# btn_single_V1_0.net
KiCad netlist of a schematic drawn in Altium Designer
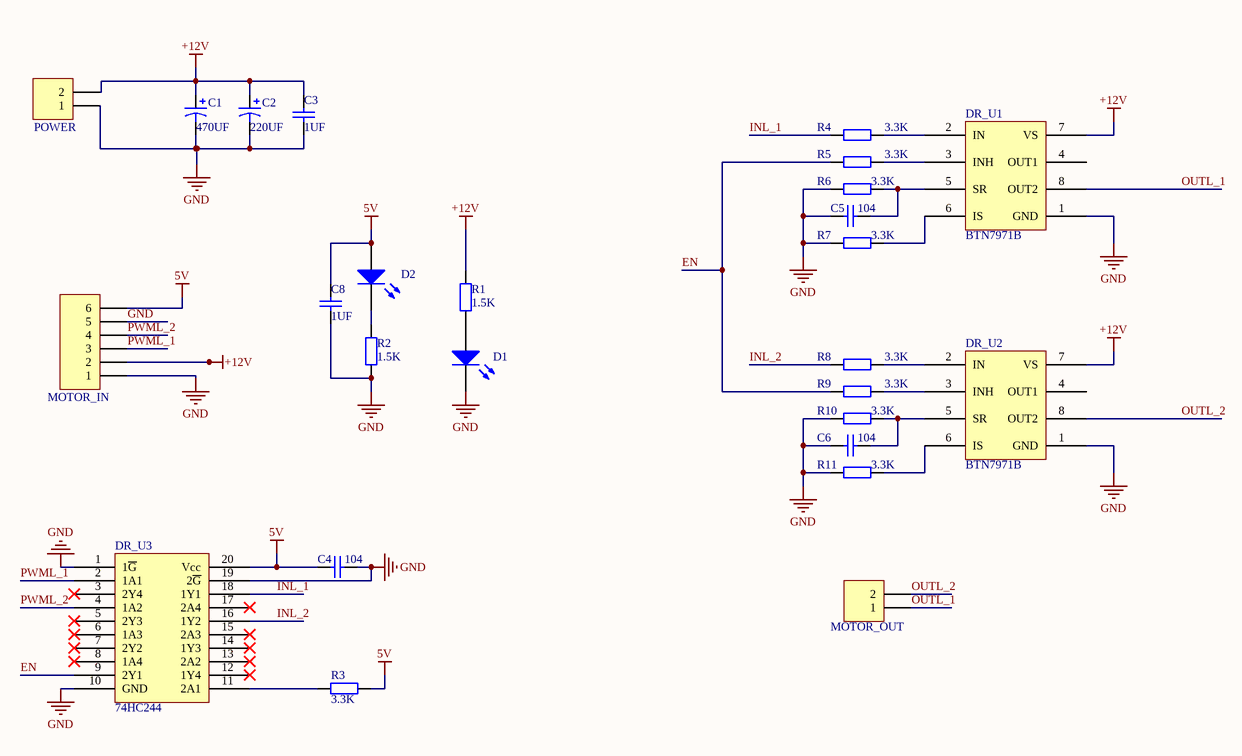
[diagram p0: btn_single_V1.0.SchDoc]

(export (version "E")
  (design (tool "Eeschema 10.0.6"))
  (components
    (comp (ref "C1")
      (value "470UF")
      (footprint "CAP 5.0*10*12.5")
      (description "Polarized Capacitor (Radial)")
      (fields (field (name "Comment") "Cap Pol1") (field (name "PUBLISHER") "Altium Limited"))
      (libsource (lib "Miscellaneous Devices") (part "Cap Pol1"))
    )
    (comp (ref "C2")
      (value "220UF")
      (footprint "CAP 2.5*6.3*7")
      (description "Polarized Capacitor (Radial)")
      (fields (field (name "Comment") "Cap Pol1") (field (name "PUBLISHER") "Altium Limited"))
      (libsource (lib "Miscellaneous Devices") (part "Cap Pol1"))
    )
    (comp (ref "C3")
      (value "1UF")
      (footprint "C 0603_L")
      (description "Capacitor")
      (fields (field (name "Comment") "Cap") (field (name "PUBLISHER") "Altium Limited"))
      (libsource (lib "Miscellaneous Devices") (part "Cap"))
    )
    (comp (ref "C4")
      (value "104")
      (footprint "C 0603_L")
      (description "Capacitor")
      (fields (field (name "Comment") "Cap") (field (name "PUBLISHER") "Altium Limited"))
      (libsource (lib "Miscellaneous Devices") (part "Cap"))
    )
    (comp (ref "C5")
      (value "104")
      (footprint "C 0603_L")
      (description "Capacitor")
      (fields (field (name "Comment") "Cap") (field (name "PUBLISHER") "Altium Limited"))
      (libsource (lib "Miscellaneous Devices") (part "Cap"))
    )
    (comp (ref "C6")
      (value "104")
      (footprint "C 0603_L")
      (description "Capacitor")
      (fields (field (name "Comment") "Cap") (field (name "PUBLISHER") "Altium Limited"))
      (libsource (lib "Miscellaneous Devices") (part "Cap"))
    )
    (comp (ref "C8")
      (value "1UF")
      (footprint "C 0603_L")
      (description "Capacitor")
      (fields (field (name "Comment") "Cap") (field (name "PUBLISHER") "Altium Limited"))
      (libsource (lib "Miscellaneous Devices") (part "Cap"))
    )
    (comp (ref "D1")
      (value "LED2")
      (footprint "0603LED B")
      (description "Typical RED, GREEN, YELLOW, AMBER GaAs LED")
      (fields (field (name "PUBLISHER") "Altium Limited"))
      (libsource (lib "Miscellaneous Devices") (part "LED2"))
    )
    (comp (ref "D2")
      (value "LED2")
      (footprint "0603LED B")
      (description "Typical RED, GREEN, YELLOW, AMBER GaAs LED")
      (fields (field (name "PUBLISHER") "Altium Limited"))
      (libsource (lib "Miscellaneous Devices") (part "LED2"))
    )
    (comp (ref "DR_U1") (value "BTN7971B") (footprint "BTN") (libsource (lib "Driver") (part "BTN7971B")))
    (comp (ref "DR_U2") (value "BTN7971B") (footprint "BTN") (libsource (lib "Driver") (part "BTN7971B")))
    (comp (ref "DR_U3") (value "74HC244") (footprint "SOP20_N") (libsource (lib "Driver") (part "74HC244")))
    (comp (ref "MOTOR_IN")
      (value "Header 6")
      (footprint "MX 1.25-WI-6P")
      (description "Header, 6-Pin")
      (fields (field (name "PUBLISHER") "Altium Limited"))
      (libsource (lib "Miscellaneous Connectors") (part "Header 6"))
    )
    (comp (ref "MOTOR_OUT")
      (value "Header 2")
      (footprint "2PIN-5.08B")
      (description "Header, 2-Pin")
      (fields (field (name "PUBLISHER") "Altium Limited"))
      (libsource (lib "Miscellaneous Connectors") (part "Header 2"))
    )
    (comp (ref "POWER")
      (value "Header 2")
      (footprint "2PIN-5.08B")
      (description "Header, 2-Pin")
      (fields (field (name "PUBLISHER") "Altium Limited"))
      (libsource (lib "Miscellaneous Connectors") (part "Header 2"))
    )
    (comp (ref "R1")
      (value "1.5K")
      (footprint "R 0603_L")
      (description "Resistor")
      (fields (field (name "Comment") "Res2") (field (name "PUBLISHER") "Altium Limited"))
      (libsource (lib "") (part "Res2_2"))
    )
    (comp (ref "R2")
      (value "1.5K")
      (footprint "R 0603_L")
      (description "Resistor")
      (fields (field (name "Comment") "Res2") (field (name "PUBLISHER") "Altium Limited"))
      (libsource (lib "") (part "Res2_2"))
    )
    (comp (ref "R3")
      (value "3.3K")
      (footprint "R 0603_L")
      (description "Resistor")
      (fields (field (name "Comment") "Res2") (field (name "PUBLISHER") "Altium Limited"))
      (libsource (lib "Miscellaneous Devices") (part "Res2"))
    )
    (comp (ref "R4")
      (value "3.3K")
      (footprint "R 0603_L")
      (description "Resistor")
      (fields (field (name "Comment") "Res2") (field (name "PUBLISHER") "Altium Limited"))
      (libsource (lib "Miscellaneous Devices") (part "Res2"))
    )
    (comp (ref "R5")
      (value "3.3K")
      (footprint "R 0603_L")
      (description "Resistor")
      (fields (field (name "Comment") "Res2") (field (name "PUBLISHER") "Altium Limited"))
      (libsource (lib "Miscellaneous Devices") (part "Res2"))
    )
    (comp (ref "R6")
      (value "3.3K")
      (footprint "R 0603_L")
      (description "Resistor")
      (fields (field (name "Comment") "Res2") (field (name "PUBLISHER") "Altium Limited"))
      (libsource (lib "") (part "Res2_1"))
    )
    (comp (ref "R7")
      (value "3.3K")
      (footprint "R 0603_L")
      (description "Resistor")
      (fields (field (name "Comment") "Res2") (field (name "PUBLISHER") "Altium Limited"))
      (libsource (lib "Miscellaneous Devices") (part "Res2"))
    )
    (comp (ref "R8")
      (value "3.3K")
      (footprint "R 0603_L")
      (description "Resistor")
      (fields (field (name "Comment") "Res2") (field (name "PUBLISHER") "Altium Limited"))
      (libsource (lib "Miscellaneous Devices") (part "Res2"))
    )
    (comp (ref "R9")
      (value "3.3K")
      (footprint "R 0603_L")
      (description "Resistor")
      (fields (field (name "Comment") "Res2") (field (name "PUBLISHER") "Altium Limited"))
      (libsource (lib "Miscellaneous Devices") (part "Res2"))
    )
    (comp (ref "R10")
      (value "3.3K")
      (footprint "R 0603_L")
      (description "Resistor")
      (fields (field (name "Comment") "Res2") (field (name "PUBLISHER") "Altium Limited"))
      (libsource (lib "") (part "Res2_1"))
    )
    (comp (ref "R11")
      (value "3.3K")
      (footprint "R 0603_L")
      (description "Resistor")
      (fields (field (name "Comment") "Res2") (field (name "PUBLISHER") "Altium Limited"))
      (libsource (lib "Miscellaneous Devices") (part "Res2"))
    )
  )
  (nets
    (net (code "1") (name "+12V") (class "Default")
      (node (ref "C1") (pin "1") (pinfunction "1_1") (pintype "passive"))
      (node (ref "C2") (pin "1") (pinfunction "1_1") (pintype "passive"))
      (node (ref "C3") (pin "1") (pinfunction "1_1") (pintype "passive"))
      (node (ref "DR_U1") (pin "7") (pinfunction "VS_7") (pintype "passive"))
      (node (ref "DR_U2") (pin "7") (pinfunction "VS_7") (pintype "passive"))
      (node (ref "MOTOR_IN") (pin "2") (pinfunction "2_2") (pintype "passive"))
      (node (ref "POWER") (pin "2") (pinfunction "2_2") (pintype "passive"))
      (node (ref "R1") (pin "2") (pinfunction "2_2") (pintype "passive"))
    )
    (net (code "2") (name "/EN") (class "Default")
      (node (ref "DR_U3") (pin "9") (pinfunction "2Y1_9") (pintype "passive"))
      (node (ref "R5") (pin "1") (pinfunction "1_1") (pintype "passive"))
      (node (ref "R9") (pin "1") (pinfunction "1_1") (pintype "passive"))
    )
    (net (code "3") (name "/INL_1") (class "Default")
      (node (ref "DR_U3") (pin "18") (pinfunction "1Y1_18") (pintype "passive"))
      (node (ref "R4") (pin "1") (pinfunction "1_1") (pintype "passive"))
    )
    (net (code "4") (name "/INL_2") (class "Default")
      (node (ref "DR_U3") (pin "16") (pinfunction "1Y2_16") (pintype "passive"))
      (node (ref "R8") (pin "1") (pinfunction "1_1") (pintype "passive"))
    )
    (net (code "5") (name "/OUTL_1") (class "Default")
      (node (ref "DR_U1") (pin "8") (pinfunction "OUT2_8") (pintype "passive"))
      (node (ref "MOTOR_OUT") (pin "1") (pinfunction "1_1") (pintype "passive"))
    )
    (net (code "6") (name "/OUTL_2") (class "Default")
      (node (ref "DR_U2") (pin "8") (pinfunction "OUT2_8") (pintype "passive"))
      (node (ref "MOTOR_OUT") (pin "2") (pinfunction "2_2") (pintype "passive"))
    )
    (net (code "7") (name "/PWML_1") (class "Default")
      (node (ref "DR_U3") (pin "2") (pinfunction "1A1_2") (pintype "passive"))
      (node (ref "MOTOR_IN") (pin "3") (pinfunction "3_3") (pintype "passive"))
    )
    (net (code "8") (name "/PWML_2") (class "Default")
      (node (ref "DR_U3") (pin "4") (pinfunction "1A2_4") (pintype "passive"))
      (node (ref "MOTOR_IN") (pin "4") (pinfunction "4_4") (pintype "passive"))
    )
    (net (code "9") (name "5V") (class "Default")
      (node (ref "C4") (pin "1") (pinfunction "1_1") (pintype "passive"))
      (node (ref "C8") (pin "1") (pinfunction "1_1") (pintype "passive"))
      (node (ref "D2") (pin "1") (pinfunction "A_1") (pintype "passive"))
      (node (ref "DR_U3") (pin "20") (pinfunction "Vcc_20") (pintype "passive"))
      (node (ref "MOTOR_IN") (pin "6") (pinfunction "6_6") (pintype "passive"))
      (node (ref "R3") (pin "2") (pinfunction "2_2") (pintype "passive"))
    )
    (net (code "10") (name "GND") (class "Default")
      (node (ref "C1") (pin "2") (pinfunction "2_2") (pintype "passive"))
      (node (ref "C2") (pin "2") (pinfunction "2_2") (pintype "passive"))
      (node (ref "C3") (pin "2") (pinfunction "2_2") (pintype "passive"))
      (node (ref "C4") (pin "2") (pinfunction "2_2") (pintype "passive"))
      (node (ref "C5") (pin "2") (pinfunction "2_2") (pintype "passive"))
      (node (ref "C6") (pin "2") (pinfunction "2_2") (pintype "passive"))
      (node (ref "C8") (pin "2") (pinfunction "2_2") (pintype "passive"))
      (node (ref "D1") (pin "2") (pinfunction "K_2") (pintype "passive"))
      (node (ref "DR_U1") (pin "1") (pinfunction "GND_1") (pintype "passive"))
      (node (ref "DR_U2") (pin "1") (pinfunction "GND_1") (pintype "passive"))
      (node (ref "DR_U3") (pin "1") (pinfunction "1~{G}_1") (pintype "passive"))
      (node (ref "DR_U3") (pin "10") (pinfunction "GND_10") (pintype "passive"))
      (node (ref "DR_U3") (pin "19") (pinfunction "2~{G}_19") (pintype "passive"))
      (node (ref "MOTOR_IN") (pin "1") (pinfunction "1_1") (pintype "passive"))
      (node (ref "MOTOR_IN") (pin "5") (pinfunction "5_5") (pintype "passive"))
      (node (ref "POWER") (pin "1") (pinfunction "1_1") (pintype "passive"))
      (node (ref "R10") (pin "2") (pinfunction "2_2") (pintype "passive"))
      (node (ref "R11") (pin "1") (pinfunction "1_1") (pintype "passive"))
      (node (ref "R2") (pin "1") (pinfunction "1_1") (pintype "passive"))
      (node (ref "R6") (pin "2") (pinfunction "2_2") (pintype "passive"))
      (node (ref "R7") (pin "1") (pinfunction "1_1") (pintype "passive"))
    )
    (net (code "11") (name "Net-(D1-A)") (class "Default")
      (node (ref "D1") (pin "1") (pinfunction "A_1") (pintype "passive"))
      (node (ref "R1") (pin "1") (pinfunction "1_1") (pintype "passive"))
    )
    (net (code "12") (name "Net-(D2-K)") (class "Default")
      (node (ref "D2") (pin "2") (pinfunction "K_2") (pintype "passive"))
      (node (ref "R2") (pin "2") (pinfunction "2_2") (pintype "passive"))
    )
    (net (code "13") (name "Net-(DR_U1-IN)") (class "Default")
      (node (ref "DR_U1") (pin "2") (pinfunction "IN_2") (pintype "passive"))
      (node (ref "R4") (pin "2") (pinfunction "2_2") (pintype "passive"))
    )
    (net (code "14") (name "Net-(DR_U1-INH)") (class "Default")
      (node (ref "DR_U1") (pin "3") (pinfunction "INH_3") (pintype "passive"))
      (node (ref "R5") (pin "2") (pinfunction "2_2") (pintype "passive"))
    )
    (net (code "15") (name "Net-(DR_U1-IS)") (class "Default")
      (node (ref "DR_U1") (pin "6") (pinfunction "IS_6") (pintype "passive"))
      (node (ref "R7") (pin "2") (pinfunction "2_2") (pintype "passive"))
    )
    (net (code "16") (name "Net-(DR_U1-SR)") (class "Default")
      (node (ref "C5") (pin "1") (pinfunction "1_1") (pintype "passive"))
      (node (ref "DR_U1") (pin "5") (pinfunction "SR_5") (pintype "passive"))
      (node (ref "R6") (pin "1") (pinfunction "1_1") (pintype "passive"))
    )
    (net (code "17") (name "Net-(DR_U2-IN)") (class "Default")
      (node (ref "DR_U2") (pin "2") (pinfunction "IN_2") (pintype "passive"))
      (node (ref "R8") (pin "2") (pinfunction "2_2") (pintype "passive"))
    )
    (net (code "18") (name "Net-(DR_U2-INH)") (class "Default")
      (node (ref "DR_U2") (pin "3") (pinfunction "INH_3") (pintype "passive"))
      (node (ref "R9") (pin "2") (pinfunction "2_2") (pintype "passive"))
    )
    (net (code "19") (name "Net-(DR_U2-IS)") (class "Default")
      (node (ref "DR_U2") (pin "6") (pinfunction "IS_6") (pintype "passive"))
      (node (ref "R11") (pin "2") (pinfunction "2_2") (pintype "passive"))
    )
    (net (code "20") (name "Net-(DR_U2-SR)") (class "Default")
      (node (ref "C6") (pin "1") (pinfunction "1_1") (pintype "passive"))
      (node (ref "DR_U2") (pin "5") (pinfunction "SR_5") (pintype "passive"))
      (node (ref "R10") (pin "1") (pinfunction "1_1") (pintype "passive"))
    )
    (net (code "21") (name "Net-(DR_U3-2A1)") (class "Default")
      (node (ref "DR_U3") (pin "11") (pinfunction "2A1_11") (pintype "passive"))
      (node (ref "R3") (pin "1") (pinfunction "1_1") (pintype "passive"))
    )
    (net (code "22") (name "unconnected-(DR_U1-OUT1-Pad4)") (class "Default")
      (node (ref "DR_U1") (pin "4") (pinfunction "OUT1_4") (pintype "passive"))
    )
    (net (code "23") (name "unconnected-(DR_U2-OUT1-Pad4)") (class "Default")
      (node (ref "DR_U2") (pin "4") (pinfunction "OUT1_4") (pintype "passive"))
    )
    (net (code "24") (name "unconnected-(DR_U3-1A3-Pad6)") (class "Default")
      (node (ref "DR_U3") (pin "6") (pinfunction "1A3_6") (pintype "passive+no_connect"))
    )
    (net (code "25") (name "unconnected-(DR_U3-1A4-Pad8)") (class "Default")
      (node (ref "DR_U3") (pin "8") (pinfunction "1A4_8") (pintype "passive+no_connect"))
    )
    (net (code "26") (name "unconnected-(DR_U3-1Y3-Pad14)") (class "Default")
      (node (ref "DR_U3") (pin "14") (pinfunction "1Y3_14") (pintype "passive+no_connect"))
    )
    (net (code "27") (name "unconnected-(DR_U3-1Y4-Pad12)") (class "Default")
      (node (ref "DR_U3") (pin "12") (pinfunction "1Y4_12") (pintype "passive+no_connect"))
    )
    (net (code "28") (name "unconnected-(DR_U3-2A2-Pad13)") (class "Default")
      (node (ref "DR_U3") (pin "13") (pinfunction "2A2_13") (pintype "passive+no_connect"))
    )
    (net (code "29") (name "unconnected-(DR_U3-2A3-Pad15)") (class "Default")
      (node (ref "DR_U3") (pin "15") (pinfunction "2A3_15") (pintype "passive+no_connect"))
    )
    (net (code "30") (name "unconnected-(DR_U3-2A4-Pad17)") (class "Default")
      (node (ref "DR_U3") (pin "17") (pinfunction "2A4_17") (pintype "passive+no_connect"))
    )
    (net (code "31") (name "unconnected-(DR_U3-2Y2-Pad7)") (class "Default")
      (node (ref "DR_U3") (pin "7") (pinfunction "2Y2_7") (pintype "passive+no_connect"))
    )
    (net (code "32") (name "unconnected-(DR_U3-2Y3-Pad5)") (class "Default")
      (node (ref "DR_U3") (pin "5") (pinfunction "2Y3_5") (pintype "passive+no_connect"))
    )
    (net (code "33") (name "unconnected-(DR_U3-2Y4-Pad3)") (class "Default")
      (node (ref "DR_U3") (pin "3") (pinfunction "2Y4_3") (pintype "passive+no_connect"))
    )
  )
)
